# ADC-ICHANNEL_GAIN_CONTROL.net
KiCad netlist of a schematic drawn in Altium Designer
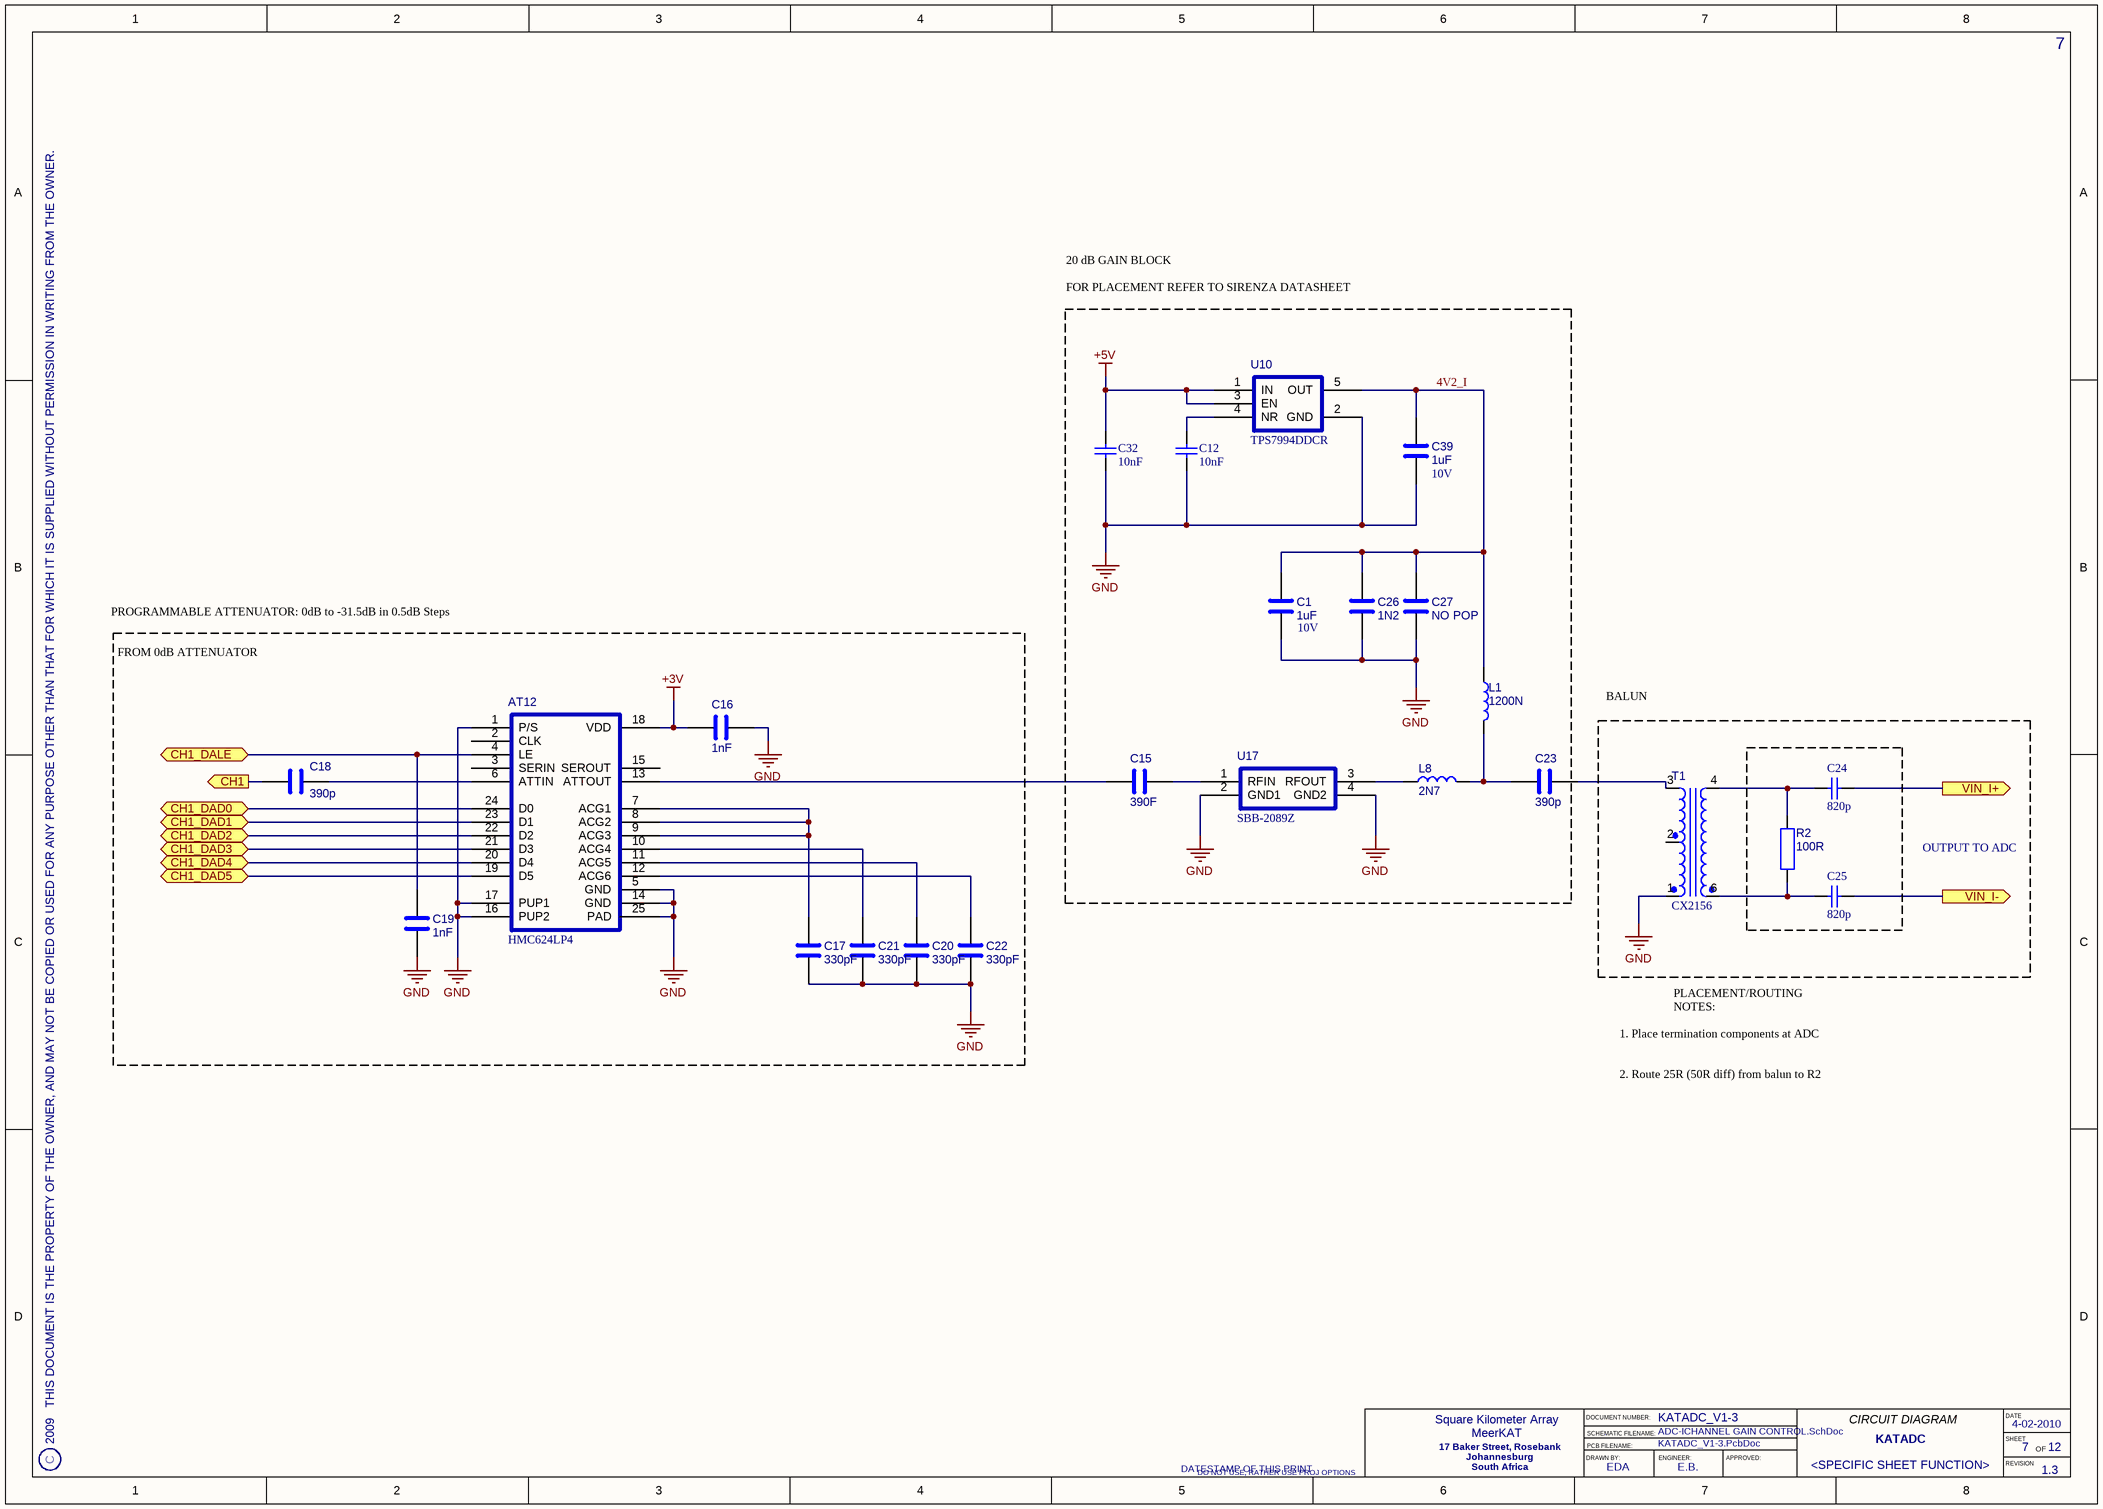
[diagram p0: ADC-ICHANNEL GAIN CONTROL.SchDoc]

(export (version "E")
  (design (tool "Eeschema 10.0.6"))
  (components
    (comp (ref "AT12")
      (value "HMC624LP4")
      (footprint "QFN50P400X400X100-25USR")
      (description "Broadband 6-bit IC Digital Attenuator")
      (fields
        (field (name "MANUFACTURER") "Hittite")
        (field (name "CREATED_BY") "IN")
        (field (name "CHECKED_BY") "NN")
        (field (name "CHECKED_DATE") "NN-08-2009")
      )
      (libsource (lib "Ishvah-TEMP") (part "HMC624LP4"))
    )
    (comp (ref "C1")
      (value "1uF")
      (footprint "CAPC1632X80USR")
      (description "CAP SMD 0603")
      (fields
        (field (name "VOLTAGE") "10V")
        (field (name "Comment") "Footprint ???")
        (field (name "CREATED_BY") "*")
        (field (name "CHECKED_BY") "*")
      )
      (libsource (lib "Abdus-TEMP") (part "CAP-0603"))
    )
    (comp (ref "C12")
      (value "10nF")
      (footprint "CAPC1005X55N")
      (description "Capacitor 0402 SMD")
      (fields (field (name "CREATED_BY") "EDA-ASA") (field (name "CHECKED_BY") "*"))
      (libsource (lib "EDA-Passive") (part "cap0402"))
    )
    (comp (ref "C15")
      (value "390F")
      (footprint "CAPC1005X55N")
      (description "CAP SMD 0603")
      (fields
        (field (name "Comment") "Footprint ???")
        (field (name "CREATED_BY") "*")
        (field (name "CHECKED_BY") "*")
      )
      (libsource (lib "Abdus-TEMP") (part "CAP-0603"))
    )
    (comp (ref "C16")
      (value "1nF")
      (footprint "0603")
      (description "CAP SMD 0603")
      (fields
        (field (name "Comment") "Footprint ???")
        (field (name "CREATED_BY") "*")
        (field (name "CHECKED_BY") "*")
      )
      (libsource (lib "Abdus-TEMP") (part "CAP-0603"))
    )
    (comp (ref "C17")
      (value "330pF")
      (footprint "0603")
      (description "CAP SMD 0603")
      (fields
        (field (name "Comment") "Footprint ???")
        (field (name "CREATED_BY") "*")
        (field (name "CHECKED_BY") "*")
      )
      (libsource (lib "Abdus-TEMP") (part "CAP-0603"))
    )
    (comp (ref "C18")
      (value "390p")
      (footprint "CAPC1005X55N")
      (description "CAP SMD 0603")
      (fields (field (name "CREATED_BY") "*") (field (name "CHECKED_BY") "*"))
      (libsource (lib "Abdus-TEMP") (part "CAP-0603"))
    )
    (comp (ref "C19")
      (value "1nF")
      (footprint "0603")
      (description "CAP SMD 0603")
      (fields (field (name "CREATED_BY") "*") (field (name "CHECKED_BY") "*"))
      (libsource (lib "Abdus-TEMP") (part "CAP-0603"))
    )
    (comp (ref "C20")
      (value "330pF")
      (footprint "0603")
      (description "CAP SMD 0603")
      (fields
        (field (name "Comment") "Footprint ???")
        (field (name "CREATED_BY") "*")
        (field (name "CHECKED_BY") "*")
      )
      (libsource (lib "Abdus-TEMP") (part "CAP-0603"))
    )
    (comp (ref "C21")
      (value "330pF")
      (footprint "0603")
      (description "CAP SMD 0603")
      (fields
        (field (name "Comment") "Footprint ???")
        (field (name "CREATED_BY") "*")
        (field (name "CHECKED_BY") "*")
      )
      (libsource (lib "Abdus-TEMP") (part "CAP-0603"))
    )
    (comp (ref "C22")
      (value "330pF")
      (footprint "0603")
      (description "CAP SMD 0603")
      (fields
        (field (name "Comment") "Footprint ???")
        (field (name "CREATED_BY") "*")
        (field (name "CHECKED_BY") "*")
      )
      (libsource (lib "Abdus-TEMP") (part "CAP-0603"))
    )
    (comp (ref "C23")
      (value "390p")
      (footprint "CAPC1005X55N")
      (description "CAP SMD 0603")
      (fields
        (field (name "Comment") "Footprint ???")
        (field (name "CREATED_BY") "*")
        (field (name "CHECKED_BY") "*")
      )
      (libsource (lib "Abdus-TEMP") (part "CAP-0603"))
    )
    (comp (ref "C24")
      (value "820p")
      (footprint "CAPC1005X55N")
      (description "Capacitor 0402 SMD")
      (fields (field (name "CREATED_BY") "EDA-ASA") (field (name "CHECKED_BY") "*"))
      (libsource (lib "EDA-Passive") (part "cap0402"))
    )
    (comp (ref "C25")
      (value "820p")
      (footprint "CAPC1005X55N")
      (description "Capacitor 0402 SMD")
      (fields (field (name "CREATED_BY") "EDA-ASA") (field (name "CHECKED_BY") "*"))
      (libsource (lib "EDA-Passive") (part "cap0402"))
    )
    (comp (ref "C26")
      (value "1N2")
      (footprint "CAPC1005X55N")
      (description "CAP SMD 0603")
      (fields (field (name "CREATED_BY") "*") (field (name "CHECKED_BY") "*"))
      (libsource (lib "Abdus-TEMP") (part "CAP-0603"))
    )
    (comp (ref "C27")
      (value "NO POP")
      (footprint "CAPC1005X55N")
      (description "CAP SMD 0603")
      (fields
        (field (name "Comment") "Footprint ???")
        (field (name "CREATED_BY") "*")
        (field (name "CHECKED_BY") "*")
      )
      (libsource (lib "Abdus-TEMP") (part "CAP-0603"))
    )
    (comp (ref "C32")
      (value "10nF")
      (footprint "CAPC1005X55N")
      (description "Capacitor 0402 SMD")
      (fields (field (name "CREATED_BY") "EDA-ASA") (field (name "CHECKED_BY") "*"))
      (libsource (lib "EDA-Passive") (part "cap0402"))
    )
    (comp (ref "C39")
      (value "1uF")
      (footprint "CAPC1632X80USR")
      (description "CAP SMD 0603")
      (fields
        (field (name "VOLTAGE") "10V")
        (field (name "Comment") "Footprint ???")
        (field (name "CREATED_BY") "*")
        (field (name "CHECKED_BY") "*")
      )
      (libsource (lib "Abdus-TEMP") (part "CAP-0603"))
    )
    (comp (ref "L1")
      (value "1200N")
      (footprint "INDM2520X160N")
      (description "CHOKE")
      (fields (field (name "CREATED_BY") "EDA-ASA") (field (name "CHECKED_BY") "*"))
      (libsource (lib "EDA_GenericSymbols") (part "CHOKE"))
    )
    (comp (ref "L8")
      (value "2N7")
      (footprint "INDC1005X60N")
      (description "CHOKE")
      (fields (field (name "CREATED_BY") "EDA-ASA") (field (name "CHECKED_BY") "*"))
      (libsource (lib "EDA_GenericSymbols") (part "CHOKE"))
    )
    (comp (ref "R2")
      (value "100R")
      (footprint "RESC1005X40N")
      (description "RESISTOR SMD 0805")
      (fields (field (name "CREATED_BY") "*") (field (name "CHECKED_BY") "NN"))
      (libsource (lib "EDA_Passive") (part "RES-0805"))
    )
    (comp (ref "T1")
      (value "CX2156")
      (footprint "PULSE_KAYAK")
      (description "TRANSFORMER WIDEBAND RF APPLICATION")
      (fields
        (field (name "VOLTAGE") "???")
        (field (name "MANUFACTURER_PN") "CX2156")
        (field (name "CREATED_BY") "*")
        (field (name "CHECKED_BY") "*")
      )
      (libsource (lib "Charles-TEMP") (part "CX2156"))
    )
    (comp (ref "U10")
      (value "TPS7994DDCR")
      (footprint "SOT95P280X110-5USR2")
      (description "Low Quiescent Current, Ultra-Low Noise Dropout Linear Regulator")
      (fields
        (field (name "MANUFACTURER") "TI")
        (field (name "CREATED_BY") "IN")
        (field (name "CHECKED_BY") "*")
      )
      (libsource (lib "Ishvah-TEMP") (part "TPS7994DDCR"))
    )
    (comp (ref "U17")
      (value "SBB-2089Z")
      (footprint "SIRENZA_SOT89")
      (description "High performance InaGaP HBT MMIC amplfier")
      (fields
        (field (name "MANUFACTURER") "Sirenza Micodevices")
        (field (name "CREATED_BY") "IN")
        (field (name "CHECKED_BY") "*")
      )
      (libsource (lib "Ishvah-TEMP") (part "SBB-2089Z"))
    )
  )
  (nets
    (net (code "1") (name "+3V") (class "Default")
      (node (ref "AT12") (pin "18") (pinfunction "VDD_18") (pintype "passive"))
      (node (ref "C16") (pin "1") (pinfunction "1_1") (pintype "passive"))
    )
    (net (code "2") (name "+5V") (class "Default")
      (node (ref "C32") (pin "1") (pinfunction "1_1") (pintype "passive"))
      (node (ref "U10") (pin "1") (pinfunction "IN_1") (pintype "passive"))
      (node (ref "U10") (pin "3") (pinfunction "EN_3") (pintype "passive"))
    )
    (net (code "3") (name "/4V2_I") (class "Default")
      (node (ref "C1") (pin "1") (pinfunction "1_1") (pintype "passive"))
      (node (ref "C26") (pin "1") (pinfunction "1_1") (pintype "passive"))
      (node (ref "C27") (pin "1") (pinfunction "1_1") (pintype "passive"))
      (node (ref "C39") (pin "1") (pinfunction "1_1") (pintype "passive"))
      (node (ref "L1") (pin "1") (pinfunction "1_1") (pintype "passive"))
      (node (ref "U10") (pin "5") (pinfunction "OUT_5") (pintype "passive"))
    )
    (net (code "4") (name "/CH1") (class "Default")
      (node (ref "C18") (pin "1") (pinfunction "1_1") (pintype "passive"))
    )
    (net (code "5") (name "/CH1_DAD0") (class "Default")
      (node (ref "AT12") (pin "24") (pinfunction "D0_24") (pintype "passive"))
    )
    (net (code "6") (name "/CH1_DAD1") (class "Default")
      (node (ref "AT12") (pin "23") (pinfunction "D1_23") (pintype "passive"))
    )
    (net (code "7") (name "/CH1_DAD2") (class "Default")
      (node (ref "AT12") (pin "22") (pinfunction "D2_22") (pintype "passive"))
    )
    (net (code "8") (name "/CH1_DAD3") (class "Default")
      (node (ref "AT12") (pin "21") (pinfunction "D3_21") (pintype "passive"))
    )
    (net (code "9") (name "/CH1_DAD4") (class "Default")
      (node (ref "AT12") (pin "20") (pinfunction "D4_20") (pintype "passive"))
    )
    (net (code "10") (name "/CH1_DAD5") (class "Default")
      (node (ref "AT12") (pin "19") (pinfunction "D5_19") (pintype "passive"))
    )
    (net (code "11") (name "/CH1_DALE") (class "Default")
      (node (ref "AT12") (pin "4") (pinfunction "LE_4") (pintype "passive"))
      (node (ref "C19") (pin "1") (pinfunction "1_1") (pintype "passive"))
    )
    (net (code "12") (name "/VIN_I+") (class "Default")
      (node (ref "C24") (pin "2") (pinfunction "2_2") (pintype "passive"))
    )
    (net (code "13") (name "/VIN_I-") (class "Default")
      (node (ref "C25") (pin "2") (pinfunction "2_2") (pintype "passive"))
    )
    (net (code "14") (name "GND") (class "Default")
      (node (ref "AT12") (pin "1") (pinfunction "P/S_1") (pintype "passive"))
      (node (ref "AT12") (pin "14") (pinfunction "GND_14") (pintype "passive"))
      (node (ref "AT12") (pin "16") (pinfunction "PUP2_16") (pintype "passive"))
      (node (ref "AT12") (pin "17") (pinfunction "PUP1_17") (pintype "passive"))
      (node (ref "AT12") (pin "25") (pinfunction "PAD_25") (pintype "passive"))
      (node (ref "AT12") (pin "5") (pinfunction "GND_5") (pintype "passive"))
      (node (ref "C1") (pin "2") (pinfunction "2_2") (pintype "passive"))
      (node (ref "C12") (pin "2") (pinfunction "2_2") (pintype "passive"))
      (node (ref "C16") (pin "2") (pinfunction "2_2") (pintype "passive"))
      (node (ref "C17") (pin "2") (pinfunction "2_2") (pintype "passive"))
      (node (ref "C19") (pin "2") (pinfunction "2_2") (pintype "passive"))
      (node (ref "C20") (pin "2") (pinfunction "2_2") (pintype "passive"))
      (node (ref "C21") (pin "2") (pinfunction "2_2") (pintype "passive"))
      (node (ref "C22") (pin "2") (pinfunction "2_2") (pintype "passive"))
      (node (ref "C26") (pin "2") (pinfunction "2_2") (pintype "passive"))
      (node (ref "C27") (pin "2") (pinfunction "2_2") (pintype "passive"))
      (node (ref "C32") (pin "2") (pinfunction "2_2") (pintype "passive"))
      (node (ref "C39") (pin "2") (pinfunction "2_2") (pintype "passive"))
      (node (ref "T1") (pin "1") (pinfunction "1_1") (pintype "passive"))
      (node (ref "U10") (pin "2") (pinfunction "GND_2") (pintype "passive"))
      (node (ref "U17") (pin "2") (pinfunction "GND1_2") (pintype "passive"))
      (node (ref "U17") (pin "4") (pinfunction "GND2_4") (pintype "passive"))
    )
    (net (code "15") (name "Net-(AT12-ACG1)") (class "Default")
      (node (ref "AT12") (pin "7") (pinfunction "ACG1_7") (pintype "passive"))
      (node (ref "AT12") (pin "8") (pinfunction "ACG2_8") (pintype "passive"))
      (node (ref "AT12") (pin "9") (pinfunction "ACG3_9") (pintype "passive"))
      (node (ref "C17") (pin "1") (pinfunction "1_1") (pintype "passive"))
    )
    (net (code "16") (name "Net-(AT12-ACG4)") (class "Default")
      (node (ref "AT12") (pin "10") (pinfunction "ACG4_10") (pintype "passive"))
      (node (ref "C21") (pin "1") (pinfunction "1_1") (pintype "passive"))
    )
    (net (code "17") (name "Net-(AT12-ACG5)") (class "Default")
      (node (ref "AT12") (pin "11") (pinfunction "ACG5_11") (pintype "passive"))
      (node (ref "C20") (pin "1") (pinfunction "1_1") (pintype "passive"))
    )
    (net (code "18") (name "Net-(AT12-ACG6)") (class "Default")
      (node (ref "AT12") (pin "12") (pinfunction "ACG6_12") (pintype "passive"))
      (node (ref "C22") (pin "1") (pinfunction "1_1") (pintype "passive"))
    )
    (net (code "19") (name "Net-(AT12-ATTIN)") (class "Default")
      (node (ref "AT12") (pin "6") (pinfunction "ATTIN_6") (pintype "passive"))
      (node (ref "C18") (pin "2") (pinfunction "2_2") (pintype "passive"))
    )
    (net (code "20") (name "Net-(AT12-ATTOUT)") (class "Default")
      (node (ref "AT12") (pin "13") (pinfunction "ATTOUT_13") (pintype "passive"))
      (node (ref "C15") (pin "1") (pinfunction "1_1") (pintype "passive"))
    )
    (net (code "21") (name "Net-(C23-Pad1)") (class "Default")
      (node (ref "C23") (pin "1") (pinfunction "1_1") (pintype "passive"))
      (node (ref "L1") (pin "2") (pinfunction "2_2") (pintype "passive"))
      (node (ref "L8") (pin "2") (pinfunction "2_2") (pintype "passive"))
    )
    (net (code "22") (name "Net-(C23-Pad2)") (class "Default")
      (node (ref "C23") (pin "2") (pinfunction "2_2") (pintype "passive"))
      (node (ref "T1") (pin "3") (pinfunction "3_3") (pintype "passive"))
    )
    (net (code "23") (name "Net-(C24-Pad1)") (class "Default")
      (node (ref "C24") (pin "1") (pinfunction "1_1") (pintype "passive"))
      (node (ref "R2") (pin "1") (pinfunction "1_1") (pintype "passive"))
      (node (ref "T1") (pin "4") (pinfunction "4_4") (pintype "passive"))
    )
    (net (code "24") (name "Net-(C25-Pad1)") (class "Default")
      (node (ref "C25") (pin "1") (pinfunction "1_1") (pintype "passive"))
      (node (ref "R2") (pin "2") (pinfunction "2_2") (pintype "passive"))
      (node (ref "T1") (pin "6") (pinfunction "6_6") (pintype "passive"))
    )
    (net (code "25") (name "Net-(U10-NR)") (class "Default")
      (node (ref "C12") (pin "1") (pinfunction "1_1") (pintype "passive"))
      (node (ref "U10") (pin "4") (pinfunction "NR_4") (pintype "passive"))
    )
    (net (code "26") (name "Net-(U17-RFIN)") (class "Default")
      (node (ref "C15") (pin "2") (pinfunction "2_2") (pintype "passive"))
      (node (ref "U17") (pin "1") (pinfunction "RFIN_1") (pintype "passive"))
    )
    (net (code "27") (name "Net-(U17-RFOUT)") (class "Default")
      (node (ref "L8") (pin "1") (pinfunction "1_1") (pintype "passive"))
      (node (ref "U17") (pin "3") (pinfunction "RFOUT_3") (pintype "passive"))
    )
    (net (code "28") (name "unconnected-(AT12-CLK-Pad2)") (class "Default")
      (node (ref "AT12") (pin "2") (pinfunction "CLK_2") (pintype "passive"))
    )
    (net (code "29") (name "unconnected-(AT12-SERIN-Pad3)") (class "Default")
      (node (ref "AT12") (pin "3") (pinfunction "SERIN_3") (pintype "passive"))
    )
    (net (code "30") (name "unconnected-(AT12-SEROUT-Pad15)") (class "Default")
      (node (ref "AT12") (pin "15") (pinfunction "SEROUT_15") (pintype "passive"))
    )
    (net (code "31") (name "unconnected-(T1-Pad2)") (class "Default")
      (node (ref "T1") (pin "2") (pinfunction "2_2") (pintype "passive"))
    )
  )
)
